# LEDS_BUTTONS_w_bar.net
KiCad netlist of a schematic drawn in Altium Designer
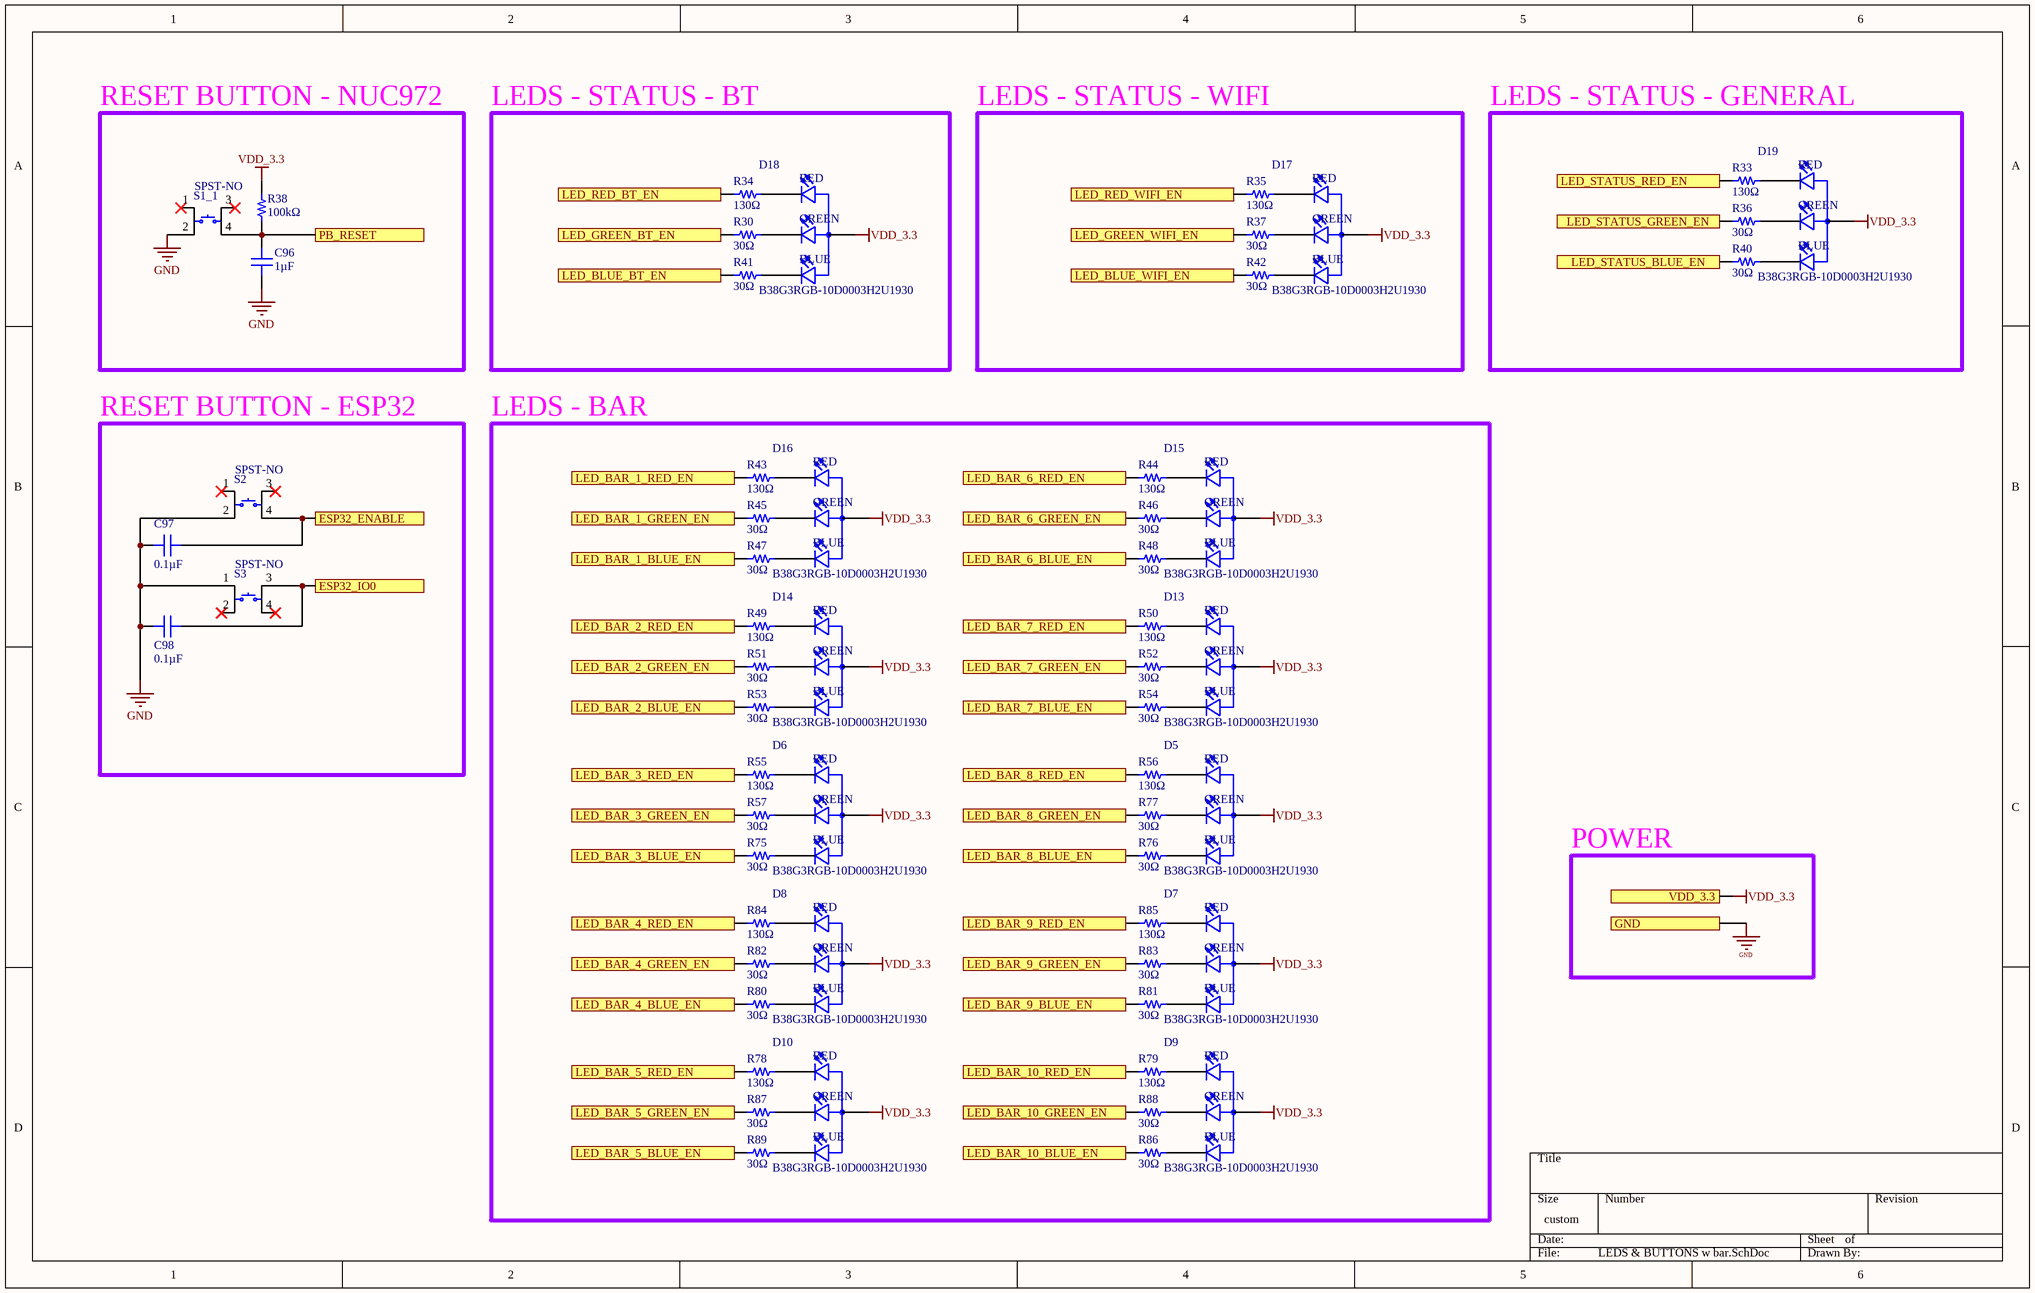
[diagram p0: LEDS & BUTTONS w bar.SchDoc]

(export (version "E")
  (design (tool "Eeschema 10.0.6"))
  (components
    (comp (ref "C96")
      (value "1µF")
      (footprint "CAP 0603_1608")
      (description "CAP CER 1UF 10V X7R 0603")
      (fields (field (name "MANUFACTURER") "KEMET") (field (name "VOLTAGE") "10V"))
      (libsource (lib "MVVVMAltiumDatabase") (part "Capacitor"))
    )
    (comp (ref "C97")
      (value "0.1µF")
      (footprint "CAP 0603_1608 RF")
      (description "CAP CER 0.1UF 16V X7R 0603")
      (fields (field (name "MANUFACTURER") "KEMET") (field (name "VOLTAGE") "16V"))
      (libsource (lib "MVVVMAltiumDatabase") (part "Capacitor"))
    )
    (comp (ref "C98")
      (value "0.1µF")
      (footprint "CAP 0603_1608 RF")
      (description "CAP CER 0.1UF 16V X7R 0603")
      (fields (field (name "MANUFACTURER") "KEMET") (field (name "VOLTAGE") "16V"))
      (libsource (lib "MVVVMAltiumDatabase") (part "Capacitor"))
    )
    (comp (ref "D5")
      (value "B38G3RGB-10D0003H2U1930")
      (footprint "LED_B38G3RGB-10D0003H2U1930")
      (description "Red, Green, Blue (RGB) - LED Indication - Discrete 2V Red, 3V Green, 3V Blue 0606 (1616 Metric)")
      (fields (field (name "MF") "Harvatek Corporation"))
      (libsource (lib "B38G3RGB-10D0003H2U1930") (part "B38G3RGB-10D0003H2U1930"))
    )
    (comp (ref "D6")
      (value "B38G3RGB-10D0003H2U1930")
      (footprint "LED_B38G3RGB-10D0003H2U1930")
      (description "Red, Green, Blue (RGB) - LED Indication - Discrete 2V Red, 3V Green, 3V Blue 0606 (1616 Metric)")
      (fields (field (name "MF") "Harvatek Corporation"))
      (libsource (lib "B38G3RGB-10D0003H2U1930") (part "B38G3RGB-10D0003H2U1930"))
    )
    (comp (ref "D7")
      (value "B38G3RGB-10D0003H2U1930")
      (footprint "LED_B38G3RGB-10D0003H2U1930")
      (description "Red, Green, Blue (RGB) - LED Indication - Discrete 2V Red, 3V Green, 3V Blue 0606 (1616 Metric)")
      (fields (field (name "MF") "Harvatek Corporation"))
      (libsource (lib "B38G3RGB-10D0003H2U1930") (part "B38G3RGB-10D0003H2U1930"))
    )
    (comp (ref "D8")
      (value "B38G3RGB-10D0003H2U1930")
      (footprint "LED_B38G3RGB-10D0003H2U1930")
      (description "Red, Green, Blue (RGB) - LED Indication - Discrete 2V Red, 3V Green, 3V Blue 0606 (1616 Metric)")
      (fields (field (name "MF") "Harvatek Corporation"))
      (libsource (lib "B38G3RGB-10D0003H2U1930") (part "B38G3RGB-10D0003H2U1930"))
    )
    (comp (ref "D9")
      (value "B38G3RGB-10D0003H2U1930")
      (footprint "LED_B38G3RGB-10D0003H2U1930")
      (description "Red, Green, Blue (RGB) - LED Indication - Discrete 2V Red, 3V Green, 3V Blue 0606 (1616 Metric)")
      (fields (field (name "MF") "Harvatek Corporation"))
      (libsource (lib "B38G3RGB-10D0003H2U1930") (part "B38G3RGB-10D0003H2U1930"))
    )
    (comp (ref "D10")
      (value "B38G3RGB-10D0003H2U1930")
      (footprint "LED_B38G3RGB-10D0003H2U1930")
      (description "Red, Green, Blue (RGB) - LED Indication - Discrete 2V Red, 3V Green, 3V Blue 0606 (1616 Metric)")
      (fields (field (name "MF") "Harvatek Corporation"))
      (libsource (lib "B38G3RGB-10D0003H2U1930") (part "B38G3RGB-10D0003H2U1930"))
    )
    (comp (ref "D13")
      (value "B38G3RGB-10D0003H2U1930")
      (footprint "LED_B38G3RGB-10D0003H2U1930")
      (description "Red, Green, Blue (RGB) - LED Indication - Discrete 2V Red, 3V Green, 3V Blue 0606 (1616 Metric)")
      (fields (field (name "MF") "Harvatek Corporation"))
      (libsource (lib "B38G3RGB-10D0003H2U1930") (part "B38G3RGB-10D0003H2U1930"))
    )
    (comp (ref "D14")
      (value "B38G3RGB-10D0003H2U1930")
      (footprint "LED_B38G3RGB-10D0003H2U1930")
      (description "Red, Green, Blue (RGB) - LED Indication - Discrete 2V Red, 3V Green, 3V Blue 0606 (1616 Metric)")
      (fields (field (name "MF") "Harvatek Corporation"))
      (libsource (lib "B38G3RGB-10D0003H2U1930") (part "B38G3RGB-10D0003H2U1930"))
    )
    (comp (ref "D15")
      (value "B38G3RGB-10D0003H2U1930")
      (footprint "LED_B38G3RGB-10D0003H2U1930")
      (description "Red, Green, Blue (RGB) - LED Indication - Discrete 2V Red, 3V Green, 3V Blue 0606 (1616 Metric)")
      (fields (field (name "MF") "Harvatek Corporation"))
      (libsource (lib "B38G3RGB-10D0003H2U1930") (part "B38G3RGB-10D0003H2U1930"))
    )
    (comp (ref "D16")
      (value "B38G3RGB-10D0003H2U1930")
      (footprint "LED_B38G3RGB-10D0003H2U1930")
      (description "Red, Green, Blue (RGB) - LED Indication - Discrete 2V Red, 3V Green, 3V Blue 0606 (1616 Metric)")
      (fields (field (name "MF") "Harvatek Corporation"))
      (libsource (lib "B38G3RGB-10D0003H2U1930") (part "B38G3RGB-10D0003H2U1930"))
    )
    (comp (ref "D17")
      (value "B38G3RGB-10D0003H2U1930")
      (footprint "LED_B38G3RGB-10D0003H2U1930")
      (description "Red, Green, Blue (RGB) - LED Indication - Discrete 2V Red, 3V Green, 3V Blue 0606 (1616 Metric)")
      (fields (field (name "MF") "Harvatek Corporation"))
      (libsource (lib "B38G3RGB-10D0003H2U1930") (part "B38G3RGB-10D0003H2U1930"))
    )
    (comp (ref "D18")
      (value "B38G3RGB-10D0003H2U1930")
      (footprint "LED_B38G3RGB-10D0003H2U1930")
      (description "Red, Green, Blue (RGB) - LED Indication - Discrete 2V Red, 3V Green, 3V Blue 0606 (1616 Metric)")
      (fields (field (name "MF") "Harvatek Corporation"))
      (libsource (lib "B38G3RGB-10D0003H2U1930") (part "B38G3RGB-10D0003H2U1930"))
    )
    (comp (ref "D19")
      (value "B38G3RGB-10D0003H2U1930")
      (footprint "LED_B38G3RGB-10D0003H2U1930")
      (description "Red, Green, Blue (RGB) - LED Indication - Discrete 2V Red, 3V Green, 3V Blue 0606 (1616 Metric)")
      (fields (field (name "MF") "Harvatek Corporation"))
      (libsource (lib "B38G3RGB-10D0003H2U1930") (part "B38G3RGB-10D0003H2U1930"))
    )
    (comp (ref "R30")
      (value "30Ω")
      (footprint "RES 0603_1608 RF")
      (description "RES 30 OHM 1% 1/10W 0603")
      (fields (field (name "MANUFACTURER") "Vishay Dale") (field (name "TOLERANCE") "±1%"))
      (libsource (lib "MVVVMAltiumDatabase") (part "Resistor"))
    )
    (comp (ref "R33")
      (value "130Ω")
      (footprint "RES 0603_1608 RF")
      (description "RES 130 OHM 1% 1/10W 0603")
      (fields (field (name "MANUFACTURER") "Vishay Dale") (field (name "TOLERANCE") "±1%"))
      (libsource (lib "MVVVMAltiumDatabase") (part "Resistor"))
    )
    (comp (ref "R34")
      (value "130Ω")
      (footprint "RES 0603_1608 RF")
      (description "RES 130 OHM 1% 1/10W 0603")
      (fields (field (name "MANUFACTURER") "Vishay Dale") (field (name "TOLERANCE") "±1%"))
      (libsource (lib "MVVVMAltiumDatabase") (part "Resistor"))
    )
    (comp (ref "R35")
      (value "130Ω")
      (footprint "RES 0603_1608 RF")
      (description "RES 130 OHM 1% 1/10W 0603")
      (fields (field (name "MANUFACTURER") "Vishay Dale") (field (name "TOLERANCE") "±1%"))
      (libsource (lib "MVVVMAltiumDatabase") (part "Resistor"))
    )
    (comp (ref "R36")
      (value "30Ω")
      (footprint "RES 0603_1608 RF")
      (description "RES 30 OHM 1% 1/10W 0603")
      (fields (field (name "MANUFACTURER") "Vishay Dale") (field (name "TOLERANCE") "±1%"))
      (libsource (lib "MVVVMAltiumDatabase") (part "Resistor"))
    )
    (comp (ref "R37")
      (value "30Ω")
      (footprint "RES 0603_1608 RF")
      (description "RES 30 OHM 1% 1/10W 0603")
      (fields (field (name "MANUFACTURER") "Vishay Dale") (field (name "TOLERANCE") "±1%"))
      (libsource (lib "MVVVMAltiumDatabase") (part "Resistor"))
    )
    (comp (ref "R38")
      (value "100kΩ")
      (footprint "RES 0402_1005 RF")
      (description "RES SMD 100K OHM 1% 1/16W 0402")
      (fields (field (name "MANUFACTURER") "Vishay Dale") (field (name "TOLERANCE") "±1%"))
      (libsource (lib "MVVVMAltiumDatabase") (part "Resistor"))
    )
    (comp (ref "R40")
      (value "30Ω")
      (footprint "RES 0603_1608 RF")
      (description "RES 30 OHM 1% 1/10W 0603")
      (fields (field (name "MANUFACTURER") "Vishay Dale") (field (name "TOLERANCE") "±1%"))
      (libsource (lib "MVVVMAltiumDatabase") (part "Resistor"))
    )
    (comp (ref "R41")
      (value "30Ω")
      (footprint "RES 0603_1608 RF")
      (description "RES 30 OHM 1% 1/10W 0603")
      (fields (field (name "MANUFACTURER") "Vishay Dale") (field (name "TOLERANCE") "±1%"))
      (libsource (lib "MVVVMAltiumDatabase") (part "Resistor"))
    )
    (comp (ref "R42")
      (value "30Ω")
      (footprint "RES 0603_1608 RF")
      (description "RES 30 OHM 1% 1/10W 0603")
      (fields (field (name "MANUFACTURER") "Vishay Dale") (field (name "TOLERANCE") "±1%"))
      (libsource (lib "MVVVMAltiumDatabase") (part "Resistor"))
    )
    (comp (ref "R43")
      (value "130Ω")
      (footprint "RES 0603_1608 RF")
      (description "RES 130 OHM 1% 1/10W 0603")
      (fields (field (name "MANUFACTURER") "Vishay Dale") (field (name "TOLERANCE") "±1%"))
      (libsource (lib "MVVVMAltiumDatabase") (part "Resistor"))
    )
    (comp (ref "R44")
      (value "130Ω")
      (footprint "RES 0603_1608 RF")
      (description "RES 130 OHM 1% 1/10W 0603")
      (fields (field (name "MANUFACTURER") "Vishay Dale") (field (name "TOLERANCE") "±1%"))
      (libsource (lib "MVVVMAltiumDatabase") (part "Resistor"))
    )
    (comp (ref "R45")
      (value "30Ω")
      (footprint "RES 0603_1608 RF")
      (description "RES 30 OHM 1% 1/10W 0603")
      (fields (field (name "MANUFACTURER") "Vishay Dale") (field (name "TOLERANCE") "±1%"))
      (libsource (lib "MVVVMAltiumDatabase") (part "Resistor"))
    )
    (comp (ref "R46")
      (value "30Ω")
      (footprint "RES 0603_1608 RF")
      (description "RES 30 OHM 1% 1/10W 0603")
      (fields (field (name "MANUFACTURER") "Vishay Dale") (field (name "TOLERANCE") "±1%"))
      (libsource (lib "MVVVMAltiumDatabase") (part "Resistor"))
    )
    (comp (ref "R47")
      (value "30Ω")
      (footprint "RES 0603_1608 RF")
      (description "RES 30 OHM 1% 1/10W 0603")
      (fields (field (name "MANUFACTURER") "Vishay Dale") (field (name "TOLERANCE") "±1%"))
      (libsource (lib "MVVVMAltiumDatabase") (part "Resistor"))
    )
    (comp (ref "R48")
      (value "30Ω")
      (footprint "RES 0603_1608 RF")
      (description "RES 30 OHM 1% 1/10W 0603")
      (fields (field (name "MANUFACTURER") "Vishay Dale") (field (name "TOLERANCE") "±1%"))
      (libsource (lib "MVVVMAltiumDatabase") (part "Resistor"))
    )
    (comp (ref "R49")
      (value "130Ω")
      (footprint "RES 0603_1608 RF")
      (description "RES 130 OHM 1% 1/10W 0603")
      (fields (field (name "MANUFACTURER") "Vishay Dale") (field (name "TOLERANCE") "±1%"))
      (libsource (lib "MVVVMAltiumDatabase") (part "Resistor"))
    )
    (comp (ref "R50")
      (value "130Ω")
      (footprint "RES 0603_1608 RF")
      (description "RES 130 OHM 1% 1/10W 0603")
      (fields (field (name "MANUFACTURER") "Vishay Dale") (field (name "TOLERANCE") "±1%"))
      (libsource (lib "MVVVMAltiumDatabase") (part "Resistor"))
    )
    (comp (ref "R51")
      (value "30Ω")
      (footprint "RES 0603_1608 RF")
      (description "RES 30 OHM 1% 1/10W 0603")
      (fields (field (name "MANUFACTURER") "Vishay Dale") (field (name "TOLERANCE") "±1%"))
      (libsource (lib "MVVVMAltiumDatabase") (part "Resistor"))
    )
    (comp (ref "R52")
      (value "30Ω")
      (footprint "RES 0603_1608 RF")
      (description "RES 30 OHM 1% 1/10W 0603")
      (fields (field (name "MANUFACTURER") "Vishay Dale") (field (name "TOLERANCE") "±1%"))
      (libsource (lib "MVVVMAltiumDatabase") (part "Resistor"))
    )
    (comp (ref "R53")
      (value "30Ω")
      (footprint "RES 0603_1608 RF")
      (description "RES 30 OHM 1% 1/10W 0603")
      (fields (field (name "MANUFACTURER") "Vishay Dale") (field (name "TOLERANCE") "±1%"))
      (libsource (lib "MVVVMAltiumDatabase") (part "Resistor"))
    )
    (comp (ref "R54")
      (value "30Ω")
      (footprint "RES 0603_1608 RF")
      (description "RES 30 OHM 1% 1/10W 0603")
      (fields (field (name "MANUFACTURER") "Vishay Dale") (field (name "TOLERANCE") "±1%"))
      (libsource (lib "MVVVMAltiumDatabase") (part "Resistor"))
    )
    (comp (ref "R55")
      (value "130Ω")
      (footprint "RES 0603_1608 RF")
      (description "RES 130 OHM 1% 1/10W 0603")
      (fields (field (name "MANUFACTURER") "Vishay Dale") (field (name "TOLERANCE") "±1%"))
      (libsource (lib "MVVVMAltiumDatabase") (part "Resistor"))
    )
    (comp (ref "R56")
      (value "130Ω")
      (footprint "RES 0603_1608 RF")
      (description "RES 130 OHM 1% 1/10W 0603")
      (fields (field (name "MANUFACTURER") "Vishay Dale") (field (name "TOLERANCE") "±1%"))
      (libsource (lib "MVVVMAltiumDatabase") (part "Resistor"))
    )
    (comp (ref "R57")
      (value "30Ω")
      (footprint "RES 0603_1608 RF")
      (description "RES 30 OHM 1% 1/10W 0603")
      (fields (field (name "MANUFACTURER") "Vishay Dale") (field (name "TOLERANCE") "±1%"))
      (libsource (lib "MVVVMAltiumDatabase") (part "Resistor"))
    )
    (comp (ref "R75")
      (value "30Ω")
      (footprint "RES 0603_1608 RF")
      (description "RES 30 OHM 1% 1/10W 0603")
      (fields (field (name "MANUFACTURER") "Vishay Dale") (field (name "TOLERANCE") "±1%"))
      (libsource (lib "MVVVMAltiumDatabase") (part "Resistor"))
    )
    (comp (ref "R76")
      (value "30Ω")
      (footprint "RES 0603_1608 RF")
      (description "RES 30 OHM 1% 1/10W 0603")
      (fields (field (name "MANUFACTURER") "Vishay Dale") (field (name "TOLERANCE") "±1%"))
      (libsource (lib "MVVVMAltiumDatabase") (part "Resistor"))
    )
    (comp (ref "R77")
      (value "30Ω")
      (footprint "RES 0603_1608 RF")
      (description "RES 30 OHM 1% 1/10W 0603")
      (fields (field (name "MANUFACTURER") "Vishay Dale") (field (name "TOLERANCE") "±1%"))
      (libsource (lib "MVVVMAltiumDatabase") (part "Resistor"))
    )
    (comp (ref "R78")
      (value "130Ω")
      (footprint "RES 0603_1608 RF")
      (description "RES 130 OHM 1% 1/10W 0603")
      (fields (field (name "MANUFACTURER") "Vishay Dale") (field (name "TOLERANCE") "±1%"))
      (libsource (lib "MVVVMAltiumDatabase") (part "Resistor"))
    )
    (comp (ref "R79")
      (value "130Ω")
      (footprint "RES 0603_1608 RF")
      (description "RES 130 OHM 1% 1/10W 0603")
      (fields (field (name "MANUFACTURER") "Vishay Dale") (field (name "TOLERANCE") "±1%"))
      (libsource (lib "MVVVMAltiumDatabase") (part "Resistor"))
    )
    (comp (ref "R80")
      (value "30Ω")
      (footprint "RES 0603_1608 RF")
      (description "RES 30 OHM 1% 1/10W 0603")
      (fields (field (name "MANUFACTURER") "Vishay Dale") (field (name "TOLERANCE") "±1%"))
      (libsource (lib "MVVVMAltiumDatabase") (part "Resistor"))
    )
    (comp (ref "R81")
      (value "30Ω")
      (footprint "RES 0603_1608 RF")
      (description "RES 30 OHM 1% 1/10W 0603")
      (fields (field (name "MANUFACTURER") "Vishay Dale") (field (name "TOLERANCE") "±1%"))
      (libsource (lib "MVVVMAltiumDatabase") (part "Resistor"))
    )
    (comp (ref "R82")
      (value "30Ω")
      (footprint "RES 0603_1608 RF")
      (description "RES 30 OHM 1% 1/10W 0603")
      (fields (field (name "MANUFACTURER") "Vishay Dale") (field (name "TOLERANCE") "±1%"))
      (libsource (lib "MVVVMAltiumDatabase") (part "Resistor"))
    )
    (comp (ref "R83")
      (value "30Ω")
      (footprint "RES 0603_1608 RF")
      (description "RES 30 OHM 1% 1/10W 0603")
      (fields (field (name "MANUFACTURER") "Vishay Dale") (field (name "TOLERANCE") "±1%"))
      (libsource (lib "MVVVMAltiumDatabase") (part "Resistor"))
    )
    (comp (ref "R84")
      (value "130Ω")
      (footprint "RES 0603_1608 RF")
      (description "RES 130 OHM 1% 1/10W 0603")
      (fields (field (name "MANUFACTURER") "Vishay Dale") (field (name "TOLERANCE") "±1%"))
      (libsource (lib "MVVVMAltiumDatabase") (part "Resistor"))
    )
    (comp (ref "R85")
      (value "130Ω")
      (footprint "RES 0603_1608 RF")
      (description "RES 130 OHM 1% 1/10W 0603")
      (fields (field (name "MANUFACTURER") "Vishay Dale") (field (name "TOLERANCE") "±1%"))
      (libsource (lib "MVVVMAltiumDatabase") (part "Resistor"))
    )
    (comp (ref "R86")
      (value "30Ω")
      (footprint "RES 0603_1608 RF")
      (description "RES 30 OHM 1% 1/10W 0603")
      (fields (field (name "MANUFACTURER") "Vishay Dale") (field (name "TOLERANCE") "±1%"))
      (libsource (lib "MVVVMAltiumDatabase") (part "Resistor"))
    )
    (comp (ref "R87")
      (value "30Ω")
      (footprint "RES 0603_1608 RF")
      (description "RES 30 OHM 1% 1/10W 0603")
      (fields (field (name "MANUFACTURER") "Vishay Dale") (field (name "TOLERANCE") "±1%"))
      (libsource (lib "MVVVMAltiumDatabase") (part "Resistor"))
    )
    (comp (ref "R88")
      (value "30Ω")
      (footprint "RES 0603_1608 RF")
      (description "RES 30 OHM 1% 1/10W 0603")
      (fields (field (name "MANUFACTURER") "Vishay Dale") (field (name "TOLERANCE") "±1%"))
      (libsource (lib "MVVVMAltiumDatabase") (part "Resistor"))
    )
    (comp (ref "R89")
      (value "30Ω")
      (footprint "RES 0603_1608 RF")
      (description "RES 30 OHM 1% 1/10W 0603")
      (fields (field (name "MANUFACTURER") "Vishay Dale") (field (name "TOLERANCE") "±1%"))
      (libsource (lib "MVVVMAltiumDatabase") (part "Resistor"))
    )
    (comp (ref "S1_1")
      (value "SPST-NO")
      (footprint "TE FSM4JSMA")
      (description "SWITCH TACTILE SPST-NO 0.05A 24V")
      (fields (field (name "MANUFACTURER") "TE Connectivity ALCOSWITCH Switches"))
      (libsource (lib "MVVVMAltiumDatabase") (part "TE FSM4JSMA"))
    )
    (comp (ref "S2")
      (value "SPST-NO")
      (footprint "TE FSM4JSMA")
      (description "SWITCH TACTILE SPST-NO 0.05A 24V")
      (fields (field (name "MANUFACTURER") "TE Connectivity ALCOSWITCH Switches"))
      (libsource (lib "MVVVMAltiumDatabase") (part "TE FSM4JSMA"))
    )
    (comp (ref "S3")
      (value "SPST-NO")
      (footprint "TE FSM4JSMA")
      (description "SWITCH TACTILE SPST-NO 0.05A 24V")
      (fields (field (name "MANUFACTURER") "TE Connectivity ALCOSWITCH Switches"))
      (libsource (lib "MVVVMAltiumDatabase") (part "TE FSM4JSMA"))
    )
  )
  (nets
    (net (code "1") (name "/ESP32_ENABLE") (class "Default")
      (node (ref "C97") (pin "1") (pinfunction "1_1") (pintype "passive"))
      (node (ref "S2") (pin "4") (pinfunction "4_4") (pintype "passive"))
    )
    (net (code "2") (name "/ESP32_IO0") (class "Default")
      (node (ref "C98") (pin "1") (pinfunction "1_1") (pintype "passive"))
      (node (ref "S3") (pin "3") (pinfunction "3_3") (pintype "passive"))
    )
    (net (code "3") (name "/LED_BAR_1_BLUE_EN") (class "Default")
      (node (ref "R47") (pin "1") (pinfunction "1_1") (pintype "passive"))
    )
    (net (code "4") (name "/LED_BAR_1_GREEN_EN") (class "Default")
      (node (ref "R45") (pin "1") (pinfunction "1_1") (pintype "passive"))
    )
    (net (code "5") (name "/LED_BAR_1_RED_EN") (class "Default")
      (node (ref "R43") (pin "1") (pinfunction "1_1") (pintype "passive"))
    )
    (net (code "6") (name "/LED_BAR_2_BLUE_EN") (class "Default")
      (node (ref "R53") (pin "1") (pinfunction "1_1") (pintype "passive"))
    )
    (net (code "7") (name "/LED_BAR_2_GREEN_EN") (class "Default")
      (node (ref "R51") (pin "1") (pinfunction "1_1") (pintype "passive"))
    )
    (net (code "8") (name "/LED_BAR_2_RED_EN") (class "Default")
      (node (ref "R49") (pin "1") (pinfunction "1_1") (pintype "passive"))
    )
    (net (code "9") (name "/LED_BAR_3_BLUE_EN") (class "Default")
      (node (ref "R75") (pin "1") (pinfunction "1_1") (pintype "passive"))
    )
    (net (code "10") (name "/LED_BAR_3_GREEN_EN") (class "Default")
      (node (ref "R57") (pin "1") (pinfunction "1_1") (pintype "passive"))
    )
    (net (code "11") (name "/LED_BAR_3_RED_EN") (class "Default")
      (node (ref "R55") (pin "1") (pinfunction "1_1") (pintype "passive"))
    )
    (net (code "12") (name "/LED_BAR_4_BLUE_EN") (class "Default")
      (node (ref "R80") (pin "1") (pinfunction "1_1") (pintype "passive"))
    )
    (net (code "13") (name "/LED_BAR_4_GREEN_EN") (class "Default")
      (node (ref "R82") (pin "1") (pinfunction "1_1") (pintype "passive"))
    )
    (net (code "14") (name "/LED_BAR_4_RED_EN") (class "Default")
      (node (ref "R84") (pin "1") (pinfunction "1_1") (pintype "passive"))
    )
    (net (code "15") (name "/LED_BAR_5_BLUE_EN") (class "Default")
      (node (ref "R89") (pin "1") (pinfunction "1_1") (pintype "passive"))
    )
    (net (code "16") (name "/LED_BAR_5_GREEN_EN") (class "Default")
      (node (ref "R87") (pin "1") (pinfunction "1_1") (pintype "passive"))
    )
    (net (code "17") (name "/LED_BAR_5_RED_EN") (class "Default")
      (node (ref "R78") (pin "1") (pinfunction "1_1") (pintype "passive"))
    )
    (net (code "18") (name "/LED_BAR_6_BLUE_EN") (class "Default")
      (node (ref "R48") (pin "1") (pinfunction "1_1") (pintype "passive"))
    )
    (net (code "19") (name "/LED_BAR_6_GREEN_EN") (class "Default")
      (node (ref "R46") (pin "1") (pinfunction "1_1") (pintype "passive"))
    )
    (net (code "20") (name "/LED_BAR_6_RED_EN") (class "Default")
      (node (ref "R44") (pin "1") (pinfunction "1_1") (pintype "passive"))
    )
    (net (code "21") (name "/LED_BAR_7_BLUE_EN") (class "Default")
      (node (ref "R54") (pin "1") (pinfunction "1_1") (pintype "passive"))
    )
    (net (code "22") (name "/LED_BAR_7_GREEN_EN") (class "Default")
      (node (ref "R52") (pin "1") (pinfunction "1_1") (pintype "passive"))
    )
    (net (code "23") (name "/LED_BAR_7_RED_EN") (class "Default")
      (node (ref "R50") (pin "1") (pinfunction "1_1") (pintype "passive"))
    )
    (net (code "24") (name "/LED_BAR_8_BLUE_EN") (class "Default")
      (node (ref "R76") (pin "1") (pinfunction "1_1") (pintype "passive"))
    )
    (net (code "25") (name "/LED_BAR_8_GREEN_EN") (class "Default")
      (node (ref "R77") (pin "1") (pinfunction "1_1") (pintype "passive"))
    )
    (net (code "26") (name "/LED_BAR_8_RED_EN") (class "Default")
      (node (ref "R56") (pin "1") (pinfunction "1_1") (pintype "passive"))
    )
    (net (code "27") (name "/LED_BAR_9_BLUE_EN") (class "Default")
      (node (ref "R81") (pin "1") (pinfunction "1_1") (pintype "passive"))
    )
    (net (code "28") (name "/LED_BAR_9_GREEN_EN") (class "Default")
      (node (ref "R83") (pin "1") (pinfunction "1_1") (pintype "passive"))
    )
    (net (code "29") (name "/LED_BAR_9_RED_EN") (class "Default")
      (node (ref "R85") (pin "1") (pinfunction "1_1") (pintype "passive"))
    )
    (net (code "30") (name "/LED_BAR_10_BLUE_EN") (class "Default")
      (node (ref "R86") (pin "1") (pinfunction "1_1") (pintype "passive"))
    )
    (net (code "31") (name "/LED_BAR_10_GREEN_EN") (class "Default")
      (node (ref "R88") (pin "1") (pinfunction "1_1") (pintype "passive"))
    )
    (net (code "32") (name "/LED_BAR_10_RED_EN") (class "Default")
      (node (ref "R79") (pin "1") (pinfunction "1_1") (pintype "passive"))
    )
    (net (code "33") (name "/LED_BLUE_BT_EN") (class "Default")
      (node (ref "R41") (pin "1") (pinfunction "1_1") (pintype "passive"))
    )
    (net (code "34") (name "/LED_BLUE_WIFI_EN") (class "Default")
      (node (ref "R42") (pin "1") (pinfunction "1_1") (pintype "passive"))
    )
    (net (code "35") (name "/LED_GREEN_BT_EN") (class "Default")
      (node (ref "R30") (pin "1") (pinfunction "1_1") (pintype "passive"))
    )
    (net (code "36") (name "/LED_GREEN_WIFI_EN") (class "Default")
      (node (ref "R37") (pin "1") (pinfunction "1_1") (pintype "passive"))
    )
    (net (code "37") (name "/LED_RED_BT_EN") (class "Default")
      (node (ref "R34") (pin "1") (pinfunction "1_1") (pintype "passive"))
    )
    (net (code "38") (name "/LED_RED_WIFI_EN") (class "Default")
      (node (ref "R35") (pin "1") (pinfunction "1_1") (pintype "passive"))
    )
    (net (code "39") (name "/LED_STATUS_BLUE_EN") (class "Default")
      (node (ref "R40") (pin "1") (pinfunction "1_1") (pintype "passive"))
    )
    (net (code "40") (name "/LED_STATUS_GREEN_EN") (class "Default")
      (node (ref "R36") (pin "1") (pinfunction "1_1") (pintype "passive"))
    )
    (net (code "41") (name "/LED_STATUS_RED_EN") (class "Default")
      (node (ref "R33") (pin "1") (pinfunction "1_1") (pintype "passive"))
    )
    (net (code "42") (name "/PB_RESET") (class "Default")
      (node (ref "C96") (pin "2") (pinfunction "2_2") (pintype "passive"))
      (node (ref "R38") (pin "1") (pinfunction "1_1") (pintype "passive"))
      (node (ref "S1_1") (pin "4") (pinfunction "4_4") (pintype "passive"))
    )
    (net (code "43") (name "GND") (class "Default")
      (node (ref "C96") (pin "1") (pinfunction "1_1") (pintype "passive"))
      (node (ref "C97") (pin "2") (pinfunction "2_2") (pintype "passive"))
      (node (ref "C98") (pin "2") (pinfunction "2_2") (pintype "passive"))
      (node (ref "S1_1") (pin "2") (pinfunction "2_2") (pintype "passive"))
      (node (ref "S2") (pin "2") (pinfunction "2_2") (pintype "passive"))
      (node (ref "S3") (pin "1") (pinfunction "1_1") (pintype "passive"))
    )
    (net (code "44") (name "Net-(D5-B_C)") (class "Default")
      (node (ref "D5") (pin "2") (pinfunction "B_C_2") (pintype "passive"))
      (node (ref "R76") (pin "2") (pinfunction "2_2") (pintype "passive"))
    )
    (net (code "45") (name "Net-(D5-G_C)") (class "Default")
      (node (ref "D5") (pin "1") (pinfunction "G_C_1") (pintype "passive"))
      (node (ref "R77") (pin "2") (pinfunction "2_2") (pintype "passive"))
    )
    (net (code "46") (name "Net-(D5-R_C)") (class "Default")
      (node (ref "D5") (pin "4") (pinfunction "R_C_4") (pintype "passive"))
      (node (ref "R56") (pin "2") (pinfunction "2_2") (pintype "passive"))
    )
    (net (code "47") (name "Net-(D6-B_C)") (class "Default")
      (node (ref "D6") (pin "2") (pinfunction "B_C_2") (pintype "passive"))
      (node (ref "R75") (pin "2") (pinfunction "2_2") (pintype "passive"))
    )
    (net (code "48") (name "Net-(D6-G_C)") (class "Default")
      (node (ref "D6") (pin "1") (pinfunction "G_C_1") (pintype "passive"))
      (node (ref "R57") (pin "2") (pinfunction "2_2") (pintype "passive"))
    )
    (net (code "49") (name "Net-(D6-R_C)") (class "Default")
      (node (ref "D6") (pin "4") (pinfunction "R_C_4") (pintype "passive"))
      (node (ref "R55") (pin "2") (pinfunction "2_2") (pintype "passive"))
    )
    (net (code "50") (name "Net-(D7-B_C)") (class "Default")
      (node (ref "D7") (pin "2") (pinfunction "B_C_2") (pintype "passive"))
      (node (ref "R81") (pin "2") (pinfunction "2_2") (pintype "passive"))
    )
    (net (code "51") (name "Net-(D7-G_C)") (class "Default")
      (node (ref "D7") (pin "1") (pinfunction "G_C_1") (pintype "passive"))
      (node (ref "R83") (pin "2") (pinfunction "2_2") (pintype "passive"))
    )
    (net (code "52") (name "Net-(D7-R_C)") (class "Default")
      (node (ref "D7") (pin "4") (pinfunction "R_C_4") (pintype "passive"))
      (node (ref "R85") (pin "2") (pinfunction "2_2") (pintype "passive"))
    )
    (net (code "53") (name "Net-(D8-B_C)") (class "Default")
      (node (ref "D8") (pin "2") (pinfunction "B_C_2") (pintype "passive"))
      (node (ref "R80") (pin "2") (pinfunction "2_2") (pintype "passive"))
    )
    (net (code "54") (name "Net-(D8-G_C)") (class "Default")
      (node (ref "D8") (pin "1") (pinfunction "G_C_1") (pintype "passive"))
      (node (ref "R82") (pin "2") (pinfunction "2_2") (pintype "passive"))
    )
    (net (code "55") (name "Net-(D8-R_C)") (class "Default")
      (node (ref "D8") (pin "4") (pinfunction "R_C_4") (pintype "passive"))
      (node (ref "R84") (pin "2") (pinfunction "2_2") (pintype "passive"))
    )
    (net (code "56") (name "Net-(D9-B_C)") (class "Default")
      (node (ref "D9") (pin "2") (pinfunction "B_C_2") (pintype "passive"))
      (node (ref "R86") (pin "2") (pinfunction "2_2") (pintype "passive"))
    )
    (net (code "57") (name "Net-(D9-G_C)") (class "Default")
      (node (ref "D9") (pin "1") (pinfunction "G_C_1") (pintype "passive"))
      (node (ref "R88") (pin "2") (pinfunction "2_2") (pintype "passive"))
    )
    (net (code "58") (name "Net-(D9-R_C)") (class "Default")
      (node (ref "D9") (pin "4") (pinfunction "R_C_4") (pintype "passive"))
      (node (ref "R79") (pin "2") (pinfunction "2_2") (pintype "passive"))
    )
    (net (code "59") (name "Net-(D10-B_C)") (class "Default")
      (node (ref "D10") (pin "2") (pinfunction "B_C_2") (pintype "passive"))
      (node (ref "R89") (pin "2") (pinfunction "2_2") (pintype "passive"))
    )
    (net (code "60") (name "Net-(D10-G_C)") (class "Default")
      (node (ref "D10") (pin "1") (pinfunction "G_C_1") (pintype "passive"))
      (node (ref "R87") (pin "2") (pinfunction "2_2") (pintype "passive"))
    )
    (net (code "61") (name "Net-(D10-R_C)") (class "Default")
      (node (ref "D10") (pin "4") (pinfunction "R_C_4") (pintype "passive"))
      (node (ref "R78") (pin "2") (pinfunction "2_2") (pintype "passive"))
    )
    (net (code "62") (name "Net-(D13-B_C)") (class "Default")
      (node (ref "D13") (pin "2") (pinfunction "B_C_2") (pintype "passive"))
      (node (ref "R54") (pin "2") (pinfunction "2_2") (pintype "passive"))
    )
    (net (code "63") (name "Net-(D13-G_C)") (class "Default")
      (node (ref "D13") (pin "1") (pinfunction "G_C_1") (pintype "passive"))
      (node (ref "R52") (pin "2") (pinfunction "2_2") (pintype "passive"))
    )
    (net (code "64") (name "Net-(D13-R_C)") (class "Default")
      (node (ref "D13") (pin "4") (pinfunction "R_C_4") (pintype "passive"))
      (node (ref "R50") (pin "2") (pinfunction "2_2") (pintype "passive"))
    )
    (net (code "65") (name "Net-(D14-B_C)") (class "Default")
      (node (ref "D14") (pin "2") (pinfunction "B_C_2") (pintype "passive"))
      (node (ref "R53") (pin "2") (pinfunction "2_2") (pintype "passive"))
    )
    (net (code "66") (name "Net-(D14-G_C)") (class "Default")
      (node (ref "D14") (pin "1") (pinfunction "G_C_1") (pintype "passive"))
      (node (ref "R51") (pin "2") (pinfunction "2_2") (pintype "passive"))
    )
    (net (code "67") (name "Net-(D14-R_C)") (class "Default")
      (node (ref "D14") (pin "4") (pinfunction "R_C_4") (pintype "passive"))
      (node (ref "R49") (pin "2") (pinfunction "2_2") (pintype "passive"))
    )
    (net (code "68") (name "Net-(D15-B_C)") (class "Default")
      (node (ref "D15") (pin "2") (pinfunction "B_C_2") (pintype "passive"))
      (node (ref "R48") (pin "2") (pinfunction "2_2") (pintype "passive"))
    )
    (net (code "69") (name "Net-(D15-G_C)") (class "Default")
      (node (ref "D15") (pin "1") (pinfunction "G_C_1") (pintype "passive"))
      (node (ref "R46") (pin "2") (pinfunction "2_2") (pintype "passive"))
    )
    (net (code "70") (name "Net-(D15-R_C)") (class "Default")
      (node (ref "D15") (pin "4") (pinfunction "R_C_4") (pintype "passive"))
      (node (ref "R44") (pin "2") (pinfunction "2_2") (pintype "passive"))
    )
    (net (code "71") (name "Net-(D16-B_C)") (class "Default")
      (node (ref "D16") (pin "2") (pinfunction "B_C_2") (pintype "passive"))
      (node (ref "R47") (pin "2") (pinfunction "2_2") (pintype "passive"))
    )
    (net (code "72") (name "Net-(D16-G_C)") (class "Default")
      (node (ref "D16") (pin "1") (pinfunction "G_C_1") (pintype "passive"))
      (node (ref "R45") (pin "2") (pinfunction "2_2") (pintype "passive"))
    )
    (net (code "73") (name "Net-(D16-R_C)") (class "Default")
      (node (ref "D16") (pin "4") (pinfunction "R_C_4") (pintype "passive"))
      (node (ref "R43") (pin "2") (pinfunction "2_2") (pintype "passive"))
    )
    (net (code "74") (name "Net-(D17-B_C)") (class "Default")
      (node (ref "D17") (pin "2") (pinfunction "B_C_2") (pintype "passive"))
      (node (ref "R42") (pin "2") (pinfunction "2_2") (pintype "passive"))
    )
    (net (code "75") (name "Net-(D17-G_C)") (class "Default")
      (node (ref "D17") (pin "1") (pinfunction "G_C_1") (pintype "passive"))
      (node (ref "R37") (pin "2") (pinfunction "2_2") (pintype "passive"))
    )
    (net (code "76") (name "Net-(D17-R_C)") (class "Default")
      (node (ref "D17") (pin "4") (pinfunction "R_C_4") (pintype "passive"))
      (node (ref "R35") (pin "2") (pinfunction "2_2") (pintype "passive"))
    )
    (net (code "77") (name "Net-(D18-B_C)") (class "Default")
      (node (ref "D18") (pin "2") (pinfunction "B_C_2") (pintype "passive"))
      (node (ref "R41") (pin "2") (pinfunction "2_2") (pintype "passive"))
    )
    (net (code "78") (name "Net-(D18-G_C)") (class "Default")
      (node (ref "D18") (pin "1") (pinfunction "G_C_1") (pintype "passive"))
      (node (ref "R30") (pin "2") (pinfunction "2_2") (pintype "passive"))
    )
    (net (code "79") (name "Net-(D18-R_C)") (class "Default")
      (node (ref "D18") (pin "4") (pinfunction "R_C_4") (pintype "passive"))
      (node (ref "R34") (pin "2") (pinfunction "2_2") (pintype "passive"))
    )
    (net (code "80") (name "Net-(D19-B_C)") (class "Default")
      (node (ref "D19") (pin "2") (pinfunction "B_C_2") (pintype "passive"))
      (node (ref "R40") (pin "2") (pinfunction "2_2") (pintype "passive"))
    )
    (net (code "81") (name "Net-(D19-G_C)") (class "Default")
      (node (ref "D19") (pin "1") (pinfunction "G_C_1") (pintype "passive"))
      (node (ref "R36") (pin "2") (pinfunction "2_2") (pintype "passive"))
    )
    (net (code "82") (name "Net-(D19-R_C)") (class "Default")
      (node (ref "D19") (pin "4") (pinfunction "R_C_4") (pintype "passive"))
      (node (ref "R33") (pin "2") (pinfunction "2_2") (pintype "passive"))
    )
    (net (code "83") (name "VDD_3.3") (class "Default")
      (node (ref "D10") (pin "3") (pinfunction "A_3") (pintype "passive"))
      (node (ref "D13") (pin "3") (pinfunction "A_3") (pintype "passive"))
      (node (ref "D14") (pin "3") (pinfunction "A_3") (pintype "passive"))
      (node (ref "D15") (pin "3") (pinfunction "A_3") (pintype "passive"))
      (node (ref "D16") (pin "3") (pinfunction "A_3") (pintype "passive"))
      (node (ref "D17") (pin "3") (pinfunction "A_3") (pintype "passive"))
      (node (ref "D18") (pin "3") (pinfunction "A_3") (pintype "passive"))
      (node (ref "D19") (pin "3") (pinfunction "A_3") (pintype "passive"))
      (node (ref "D5") (pin "3") (pinfunction "A_3") (pintype "passive"))
      (node (ref "D6") (pin "3") (pinfunction "A_3") (pintype "passive"))
      (node (ref "D7") (pin "3") (pinfunction "A_3") (pintype "passive"))
      (node (ref "D8") (pin "3") (pinfunction "A_3") (pintype "passive"))
      (node (ref "D9") (pin "3") (pinfunction "A_3") (pintype "passive"))
      (node (ref "R38") (pin "2") (pinfunction "2_2") (pintype "passive"))
    )
    (net (code "84") (name "unconnected-(S1_1-Pad1)") (class "Default")
      (node (ref "S1_1") (pin "1") (pinfunction "1_1") (pintype "passive+no_connect"))
    )
    (net (code "85") (name "unconnected-(S1_1-Pad3)") (class "Default")
      (node (ref "S1_1") (pin "3") (pinfunction "3_3") (pintype "passive+no_connect"))
    )
    (net (code "86") (name "unconnected-(S2-Pad1)") (class "Default")
      (node (ref "S2") (pin "1") (pinfunction "1_1") (pintype "passive+no_connect"))
    )
    (net (code "87") (name "unconnected-(S2-Pad3)") (class "Default")
      (node (ref "S2") (pin "3") (pinfunction "3_3") (pintype "passive+no_connect"))
    )
    (net (code "88") (name "unconnected-(S3-Pad2)") (class "Default")
      (node (ref "S3") (pin "2") (pinfunction "2_2") (pintype "passive+no_connect"))
    )
    (net (code "89") (name "unconnected-(S3-Pad4)") (class "Default")
      (node (ref "S3") (pin "4") (pinfunction "4_4") (pintype "passive+no_connect"))
    )
  )
)
